# Connector.net
KiCad netlist of a schematic drawn in Altium Designer
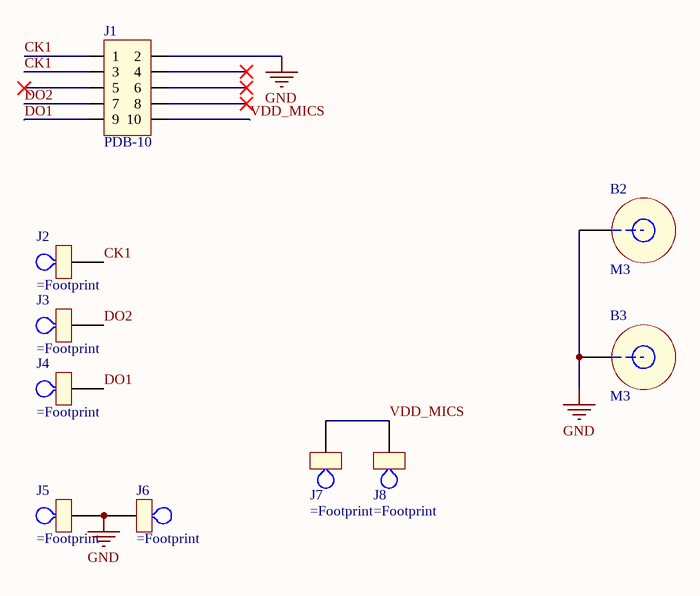
[diagram p0: Connector.SchDoc]

(export (version "E")
  (design (tool "Eeschema 10.0.6"))
  (components
    (comp (ref "B2")
      (value "M3")
      (footprint "M3_Plated_Hole_NO_3D")
      (description "Machine Screw, M3")
      (libsource (lib "FastenersAndFixings") (part "M3"))
    )
    (comp (ref "B3")
      (value "M3")
      (footprint "M3_Plated_Hole_NO_3D")
      (description "Machine Screw, M3")
      (libsource (lib "FastenersAndFixings") (part "M3"))
    )
    (comp (ref "J1") (value "PDB-10") (footprint "PDB-10") (libsource (lib "Components") (part "PDB-10")))
    (comp (ref "J2") (value "~") (footprint "5001") (libsource (lib "Connectors") (part "Test_Point")))
    (comp (ref "J3") (value "~") (footprint "5001") (libsource (lib "Connectors") (part "Test_Point")))
    (comp (ref "J4") (value "~") (footprint "5001") (libsource (lib "Connectors") (part "Test_Point")))
    (comp (ref "J5") (value "~") (footprint "5001") (libsource (lib "Connectors") (part "Test_Point")))
    (comp (ref "J6") (value "~") (footprint "5001") (libsource (lib "") (part "Test_Point_2")))
    (comp (ref "J7") (value "~") (footprint "5001") (libsource (lib "") (part "Test_Point_1")))
    (comp (ref "J8") (value "~") (footprint "5001") (libsource (lib "") (part "Test_Point_1")))
  )
  (nets
    (net (code "1") (name "/CK1") (class "Default")
      (node (ref "J1") (pin "1") (pinfunction "1_1") (pintype "passive"))
      (node (ref "J1") (pin "3") (pinfunction "3_3") (pintype "passive"))
      (node (ref "J2") (pin "1") (pinfunction "1_1") (pintype "passive"))
    )
    (net (code "2") (name "/DO1") (class "Default")
      (node (ref "J1") (pin "9") (pinfunction "9_9") (pintype "passive"))
      (node (ref "J4") (pin "1") (pinfunction "1_1") (pintype "passive"))
    )
    (net (code "3") (name "/DO2") (class "Default")
      (node (ref "J1") (pin "7") (pinfunction "7_7") (pintype "passive"))
      (node (ref "J3") (pin "1") (pinfunction "1_1") (pintype "passive"))
    )
    (net (code "4") (name "/VDD_MICS") (class "Default")
      (node (ref "J1") (pin "10") (pinfunction "10_10") (pintype "passive"))
      (node (ref "J7") (pin "1") (pinfunction "1_1") (pintype "passive"))
      (node (ref "J8") (pin "1") (pinfunction "1_1") (pintype "passive"))
    )
    (net (code "5") (name "GND") (class "Default")
      (node (ref "B2") (pin "1") (pinfunction "1_1") (pintype "passive"))
      (node (ref "B3") (pin "1") (pinfunction "1_1") (pintype "passive"))
      (node (ref "J1") (pin "2") (pinfunction "2_2") (pintype "passive"))
      (node (ref "J5") (pin "1") (pinfunction "1_1") (pintype "passive"))
      (node (ref "J6") (pin "1") (pinfunction "1_1") (pintype "passive"))
    )
    (net (code "6") (name "unconnected-(J1-Pad4)") (class "Default")
      (node (ref "J1") (pin "4") (pinfunction "4_4") (pintype "passive+no_connect"))
    )
    (net (code "7") (name "unconnected-(J1-Pad5)") (class "Default")
      (node (ref "J1") (pin "5") (pinfunction "5_5") (pintype "passive+no_connect"))
    )
    (net (code "8") (name "unconnected-(J1-Pad6)") (class "Default")
      (node (ref "J1") (pin "6") (pinfunction "6_6") (pintype "passive+no_connect"))
    )
    (net (code "9") (name "unconnected-(J1-Pad8)") (class "Default")
      (node (ref "J1") (pin "8") (pinfunction "8_8") (pintype "passive+no_connect"))
    )
  )
)
